# LCL_1.net
KiCad netlist of a schematic drawn in Altium Designer
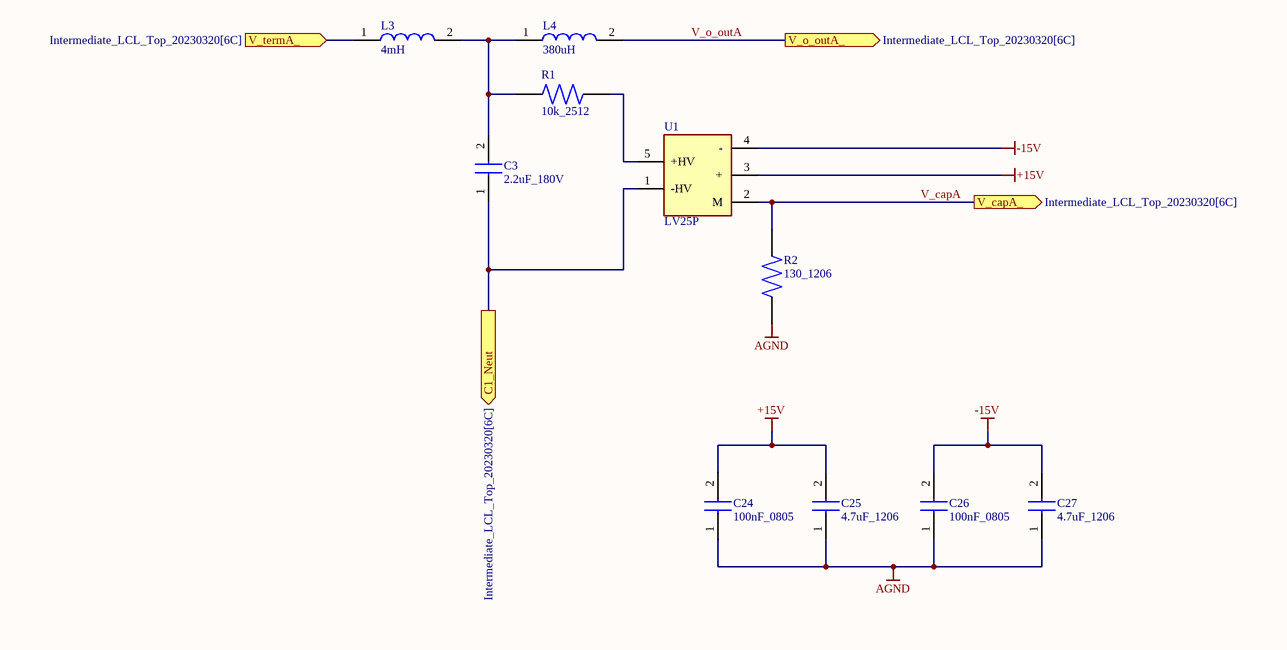
[diagram p0: LCL_1.SchDoc]

(export (version "E")
  (design (tool "Eeschema 10.0.6"))
  (components
    (comp (ref "C3")
      (value "2.2uF_180V")
      (footprint "Film Capacitor PHE450HF7220JR06L2")
      (description "KEMET PHE450 Metallised Polypropylene Film Capacitor, 180 V ac, 250 V dc, ±5%, 2.2μF, Through Hole")
      (fields (field (name "MANUFACTURER_PART_NUMBER") "PHE450HF7220JR06L2"))
      (libsource (lib "FYP_Components") (part "PHE450HF7220JR06L2"))
    )
    (comp (ref "C24")
      (value "100nF_0805")
      (footprint "0805 Capacitor")
      (description "SMD Multilayer Ceramic Capacitor, 0.1 µF, 50 V, 0805 [2012 Metric], ± 5%, X7R, C Series KEMET")
      (libsource (lib "FYP_Components") (part "C0805C104J5RACTU"))
    )
    (comp (ref "C25")
      (value "4.7uF_1206")
      (footprint "FYP_Components:1206 Capacitor")
      (description "SMD Multilayer Ceramic Capacitor, 4.7 µF, 50 V, 1206 [3216 Metric], ± 10%, X7R, C")
      (fields (field (name "MP") "C1206C120J5GACTU"))
      (libsource (lib "FYP_Components") (part "C3216X7R1H475K160AC"))
    )
    (comp (ref "C26")
      (value "100nF_0805")
      (footprint "0805 Capacitor")
      (description "SMD Multilayer Ceramic Capacitor, 0.1 µF, 50 V, 0805 [2012 Metric], ± 5%, X7R, C Series KEMET")
      (libsource (lib "FYP_Components") (part "C0805C104J5RACTU"))
    )
    (comp (ref "C27")
      (value "4.7uF_1206")
      (footprint "FYP_Components:1206 Capacitor")
      (description "SMD Multilayer Ceramic Capacitor, 4.7 µF, 50 V, 1206 [3216 Metric], ± 10%, X7R, C")
      (fields (field (name "MP") "C1206C120J5GACTU"))
      (libsource (lib "FYP_Components") (part "C3216X7R1H475K160AC"))
    )
    (comp (ref "L3")
      (value "4mH")
      (footprint "4mH Custom")
      (libsource (lib "FYP_Components") (part "4mH Custom Inductor"))
    )
    (comp (ref "L4")
      (value "380uH")
      (footprint "380uH Custom")
      (libsource (lib "FYP_Components") (part "380uH Custom Inductor"))
    )
    (comp (ref "R1")
      (value "10k_2512")
      (footprint "FYP_Components:2512 Resistor")
      (description "SMD Chip Resistor, 10 kohm, ± 1%, 2 W, 2512 [6432 Metric], Thick Film, High Power")
      (fields (field (name "MF") "Bourns") (field (name "MP") "CRE2512-FZ-R007E-3"))
      (libsource (lib "FYP_Components") (part "MCHP122WF1002T4E"))
    )
    (comp (ref "R2")
      (value "130_1206")
      (footprint "FYP_Components:1206 Resistor")
      (description "SMD Chip Resistor, 130 ohm, ± 1%, 250 mW, 1206 [3216 Metric], Thick Film, General Purpose")
      (fields (field (name "MF") "Bourns") (field (name "MP") "CRE2512-FZ-R007E-3"))
      (libsource (lib "FYP_Components") (part "CRCW1206130RFKEA"))
    )
    (comp (ref "U1")
      (value "LV25P")
      (footprint "FYP_Components:LV-25-P")
      (description "Undefined or Miscellaneous")
      (libsource (lib "FYP_Components") (part "LV25P"))
    )
  )
  (nets
    (net (code "1") (name "+15V") (class "Default")
      (node (ref "C24") (pin "2") (pinfunction "2_2") (pintype "passive"))
      (node (ref "C25") (pin "2") (pinfunction "2_2") (pintype "passive"))
      (node (ref "U1") (pin "3") (pinfunction "+_3") (pintype "passive"))
    )
    (net (code "2") (name "-15V") (class "Default")
      (node (ref "C26") (pin "2") (pinfunction "2_2") (pintype "passive"))
      (node (ref "C27") (pin "2") (pinfunction "2_2") (pintype "passive"))
      (node (ref "U1") (pin "4") (pinfunction "-_4") (pintype "passive"))
    )
    (net (code "3") (name "/C1_Neut") (class "Default")
      (node (ref "C3") (pin "1") (pinfunction "1_1") (pintype "passive"))
      (node (ref "U1") (pin "1") (pinfunction "-HV_1") (pintype "passive"))
    )
    (net (code "4") (name "/V_capA") (class "Default")
      (node (ref "R2") (pin "2") (pinfunction "2_2") (pintype "passive"))
      (node (ref "U1") (pin "2") (pinfunction "M_2") (pintype "passive"))
    )
    (net (code "5") (name "/V_o_outA") (class "Default")
      (node (ref "L4") (pin "2") (pinfunction "2_2") (pintype "passive"))
    )
    (net (code "6") (name "/V_termA_") (class "Default")
      (node (ref "L3") (pin "1") (pinfunction "1_1") (pintype "passive"))
    )
    (net (code "7") (name "AGND") (class "Default")
      (node (ref "C24") (pin "1") (pinfunction "1_1") (pintype "passive"))
      (node (ref "C25") (pin "1") (pinfunction "1_1") (pintype "passive"))
      (node (ref "C26") (pin "1") (pinfunction "1_1") (pintype "passive"))
      (node (ref "C27") (pin "1") (pinfunction "1_1") (pintype "passive"))
      (node (ref "R2") (pin "1") (pinfunction "1_1") (pintype "passive"))
    )
    (net (code "8") (name "Net-(C3-Pad2)") (class "Default")
      (node (ref "C3") (pin "2") (pinfunction "2_2") (pintype "passive"))
      (node (ref "L3") (pin "2") (pinfunction "2_2") (pintype "passive"))
      (node (ref "L4") (pin "1") (pinfunction "1_1") (pintype "passive"))
      (node (ref "R1") (pin "1") (pinfunction "1_1") (pintype "passive"))
    )
    (net (code "9") (name "Net-(U1-+HV)") (class "Default")
      (node (ref "R1") (pin "2") (pinfunction "2_2") (pintype "passive"))
      (node (ref "U1") (pin "5") (pinfunction "+HV_5") (pintype "passive"))
    )
  )
)
